# 7_-_CONNECTORS.net
KiCad netlist of a schematic drawn in Altium Designer
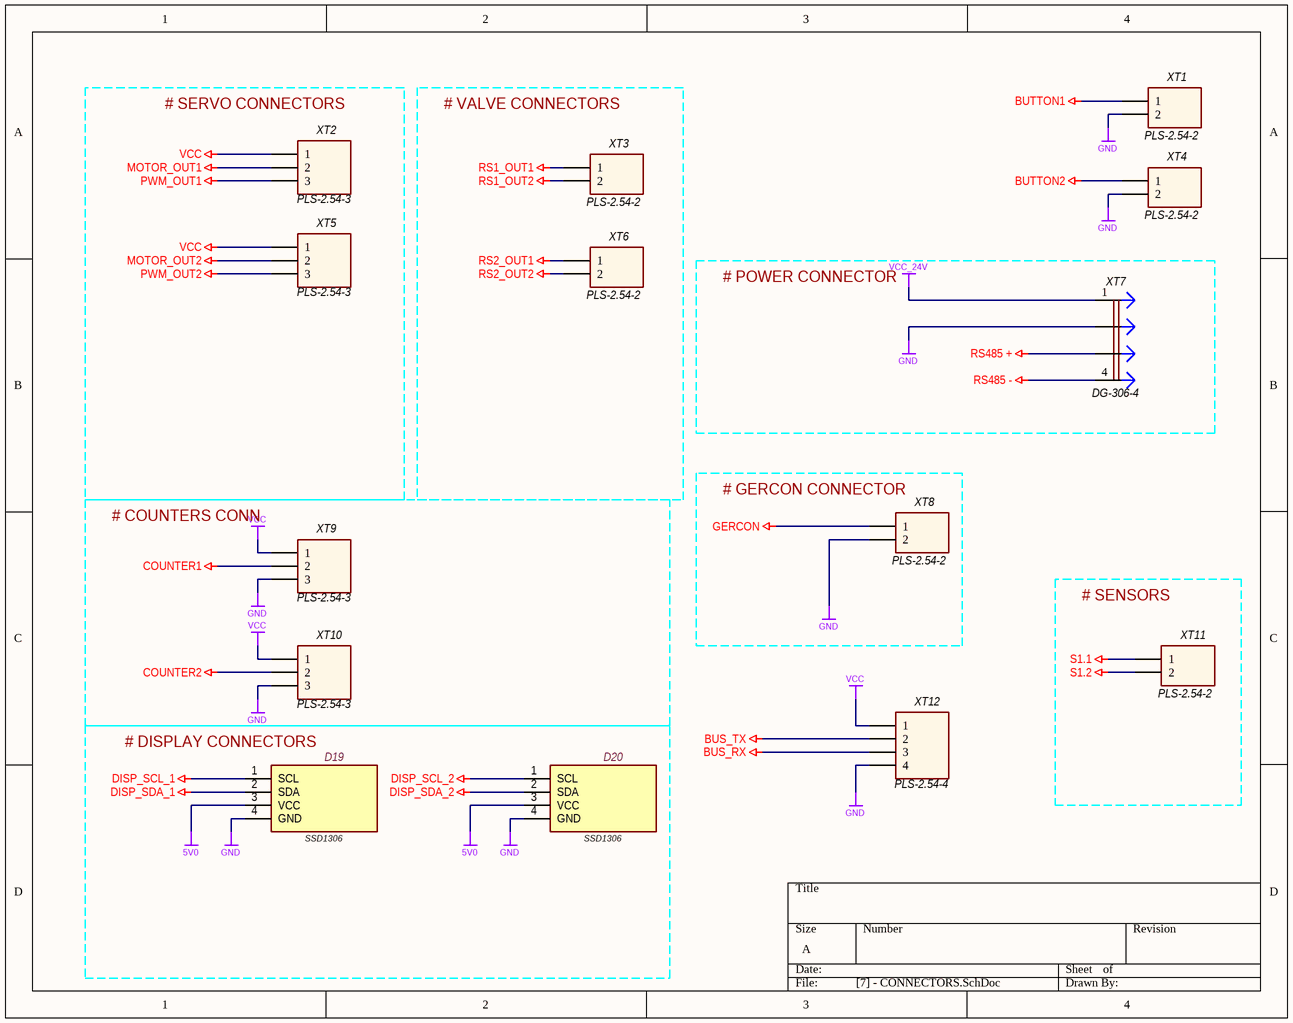
[diagram p0: [7] - CONNECTORS.SchDoc]

(export (version "E")
  (design (tool "Eeschema 10.0.6"))
  (components
    (comp (ref "D19")
      (value "SSD1306")
      (footprint "SSD1306")
      (description "0.91″ min OLED display screen with 128X32 resoluction and SSD1306 chipset")
      (libsource (lib "Modules") (part "SSD1306"))
    )
    (comp (ref "D20")
      (value "SSD1306")
      (footprint "SSD1306")
      (description "0.91″ min OLED display screen with 128X32 resoluction and SSD1306 chipset")
      (libsource (lib "Modules") (part "SSD1306"))
    )
    (comp (ref "XT1")
      (value "PLS-2.54-2")
      (footprint "HeaderConnectors:J1x2")
      (description "Header Connector  2.54 mm")
      (libsource (lib "Connectors") (part "PLS-2.54-2"))
    )
    (comp (ref "XT2")
      (value "PLS-2.54-3")
      (footprint "HeaderConnectors:J1x3")
      (description "Header Connector  2.54 mm")
      (libsource (lib "Connectors") (part "PLS-2.54-3"))
    )
    (comp (ref "XT3")
      (value "PLS-2.54-2")
      (footprint "HeaderConnectors:J1x2")
      (description "Header Connector  2.54 mm")
      (libsource (lib "Connectors") (part "PLS-2.54-2"))
    )
    (comp (ref "XT4")
      (value "PLS-2.54-2")
      (footprint "HeaderConnectors:J1x2")
      (description "Header Connector  2.54 mm")
      (libsource (lib "Connectors") (part "PLS-2.54-2"))
    )
    (comp (ref "XT5")
      (value "PLS-2.54-3")
      (footprint "HeaderConnectors:J1x3")
      (description "Header Connector  2.54 mm")
      (libsource (lib "Connectors") (part "PLS-2.54-3"))
    )
    (comp (ref "XT6")
      (value "PLS-2.54-2")
      (footprint "HeaderConnectors:J1x2")
      (description "Header Connector  2.54 mm")
      (libsource (lib "Connectors") (part "PLS-2.54-2"))
    )
    (comp (ref "XT7")
      (value "DG-306-4")
      (description "Terminal Block 5.08mm")
      (libsource (lib "Connectors") (part "DG-306-4"))
    )
    (comp (ref "XT8")
      (value "PLS-2.54-2")
      (footprint "HeaderConnectors:J1x2")
      (description "Header Connector  2.54 mm")
      (libsource (lib "Connectors") (part "PLS-2.54-2"))
    )
    (comp (ref "XT9")
      (value "PLS-2.54-3")
      (footprint "HeaderConnectors:J1x3")
      (description "Header Connector  2.54 mm")
      (libsource (lib "Connectors") (part "PLS-2.54-3"))
    )
    (comp (ref "XT10")
      (value "PLS-2.54-3")
      (footprint "HeaderConnectors:J1x3")
      (description "Header Connector  2.54 mm")
      (libsource (lib "Connectors") (part "PLS-2.54-3"))
    )
    (comp (ref "XT11")
      (value "PLS-2.54-2")
      (footprint "HeaderConnectors:J1x2")
      (description "Header Connector  2.54 mm")
      (libsource (lib "Connectors") (part "PLS-2.54-2"))
    )
    (comp (ref "XT12")
      (value "PLS-2.54-4")
      (footprint "HeaderConnectors:J1x4")
      (description "Header Connector  2.54 mm")
      (libsource (lib "Connectors") (part "PLS-2.54-4"))
    )
  )
  (nets
    (net (code "1") (name "5V0") (class "Default")
      (node (ref "D19") (pin "3") (pinfunction "VCC_3") (pintype "passive"))
      (node (ref "D20") (pin "3") (pinfunction "VCC_3") (pintype "passive"))
    )
    (net (code "2") (name "BUS_RX") (class "Default")
      (node (ref "XT12") (pin "3") (pinfunction "3_3") (pintype "passive"))
    )
    (net (code "3") (name "BUS_TX") (class "Default")
      (node (ref "XT12") (pin "2") (pinfunction "2_2") (pintype "passive"))
    )
    (net (code "4") (name "BUTTON1") (class "Default")
      (node (ref "XT1") (pin "1") (pinfunction "1_1") (pintype "passive"))
    )
    (net (code "5") (name "BUTTON2") (class "Default")
      (node (ref "XT4") (pin "1") (pinfunction "1_1") (pintype "passive"))
    )
    (net (code "6") (name "COUNTER1") (class "Default")
      (node (ref "XT9") (pin "2") (pinfunction "2_2") (pintype "passive"))
    )
    (net (code "7") (name "COUNTER2") (class "Default")
      (node (ref "XT10") (pin "2") (pinfunction "2_2") (pintype "passive"))
    )
    (net (code "8") (name "DISP_SCL_1") (class "Default")
      (node (ref "D19") (pin "1") (pinfunction "SCL_1") (pintype "passive"))
    )
    (net (code "9") (name "DISP_SCL_2") (class "Default")
      (node (ref "D20") (pin "1") (pinfunction "SCL_1") (pintype "passive"))
    )
    (net (code "10") (name "DISP_SDA_1") (class "Default")
      (node (ref "D19") (pin "2") (pinfunction "SDA_2") (pintype "passive"))
    )
    (net (code "11") (name "DISP_SDA_2") (class "Default")
      (node (ref "D20") (pin "2") (pinfunction "SDA_2") (pintype "passive"))
    )
    (net (code "12") (name "GERCON") (class "Default")
      (node (ref "XT8") (pin "1") (pinfunction "1_1") (pintype "passive"))
    )
    (net (code "13") (name "GND") (class "Default")
      (node (ref "D19") (pin "4") (pinfunction "GND_4") (pintype "passive"))
      (node (ref "D20") (pin "4") (pinfunction "GND_4") (pintype "passive"))
      (node (ref "XT1") (pin "2") (pinfunction "2_2") (pintype "passive"))
      (node (ref "XT10") (pin "3") (pinfunction "3_3") (pintype "passive"))
      (node (ref "XT12") (pin "4") (pinfunction "4_4") (pintype "passive"))
      (node (ref "XT4") (pin "2") (pinfunction "2_2") (pintype "passive"))
      (node (ref "XT7") (pin "2") (pinfunction "2_2") (pintype "passive"))
      (node (ref "XT8") (pin "2") (pinfunction "2_2") (pintype "passive"))
      (node (ref "XT9") (pin "3") (pinfunction "3_3") (pintype "passive"))
    )
    (net (code "14") (name "MOTOR_OUT1") (class "Default")
      (node (ref "XT2") (pin "2") (pinfunction "2_2") (pintype "passive"))
    )
    (net (code "15") (name "MOTOR_OUT2") (class "Default")
      (node (ref "XT5") (pin "2") (pinfunction "2_2") (pintype "passive"))
    )
    (net (code "16") (name "PWM_OUT1") (class "Default")
      (node (ref "XT2") (pin "3") (pinfunction "3_3") (pintype "passive"))
    )
    (net (code "17") (name "PWM_OUT2") (class "Default")
      (node (ref "XT5") (pin "3") (pinfunction "3_3") (pintype "passive"))
    )
    (net (code "18") (name "RS1_OUT1") (class "Default")
      (node (ref "XT3") (pin "1") (pinfunction "1_1") (pintype "passive"))
    )
    (net (code "19") (name "RS1_OUT2") (class "Default")
      (node (ref "XT3") (pin "2") (pinfunction "2_2") (pintype "passive"))
    )
    (net (code "20") (name "RS2_OUT1") (class "Default")
      (node (ref "XT6") (pin "1") (pinfunction "1_1") (pintype "passive"))
    )
    (net (code "21") (name "RS2_OUT2") (class "Default")
      (node (ref "XT6") (pin "2") (pinfunction "2_2") (pintype "passive"))
    )
    (net (code "22") (name "RS485 +") (class "Default")
      (node (ref "XT7") (pin "3") (pinfunction "3_3") (pintype "passive"))
    )
    (net (code "23") (name "RS485 -") (class "Default")
      (node (ref "XT7") (pin "4") (pinfunction "4_4") (pintype "passive"))
    )
    (net (code "24") (name "S1.1") (class "Default")
      (node (ref "XT11") (pin "1") (pinfunction "1_1") (pintype "passive"))
    )
    (net (code "25") (name "S1.2") (class "Default")
      (node (ref "XT11") (pin "2") (pinfunction "2_2") (pintype "passive"))
    )
    (net (code "26") (name "VCC") (class "Default")
      (node (ref "XT10") (pin "1") (pinfunction "1_1") (pintype "passive"))
      (node (ref "XT12") (pin "1") (pinfunction "1_1") (pintype "passive"))
      (node (ref "XT2") (pin "1") (pinfunction "1_1") (pintype "passive"))
      (node (ref "XT5") (pin "1") (pinfunction "1_1") (pintype "passive"))
      (node (ref "XT9") (pin "1") (pinfunction "1_1") (pintype "passive"))
    )
    (net (code "27") (name "VCC_24V") (class "Default")
      (node (ref "XT7") (pin "1") (pinfunction "1_1") (pintype "passive"))
    )
  )
)
